# biochem_M.net
KiCad netlist of a schematic drawn in EAGLE
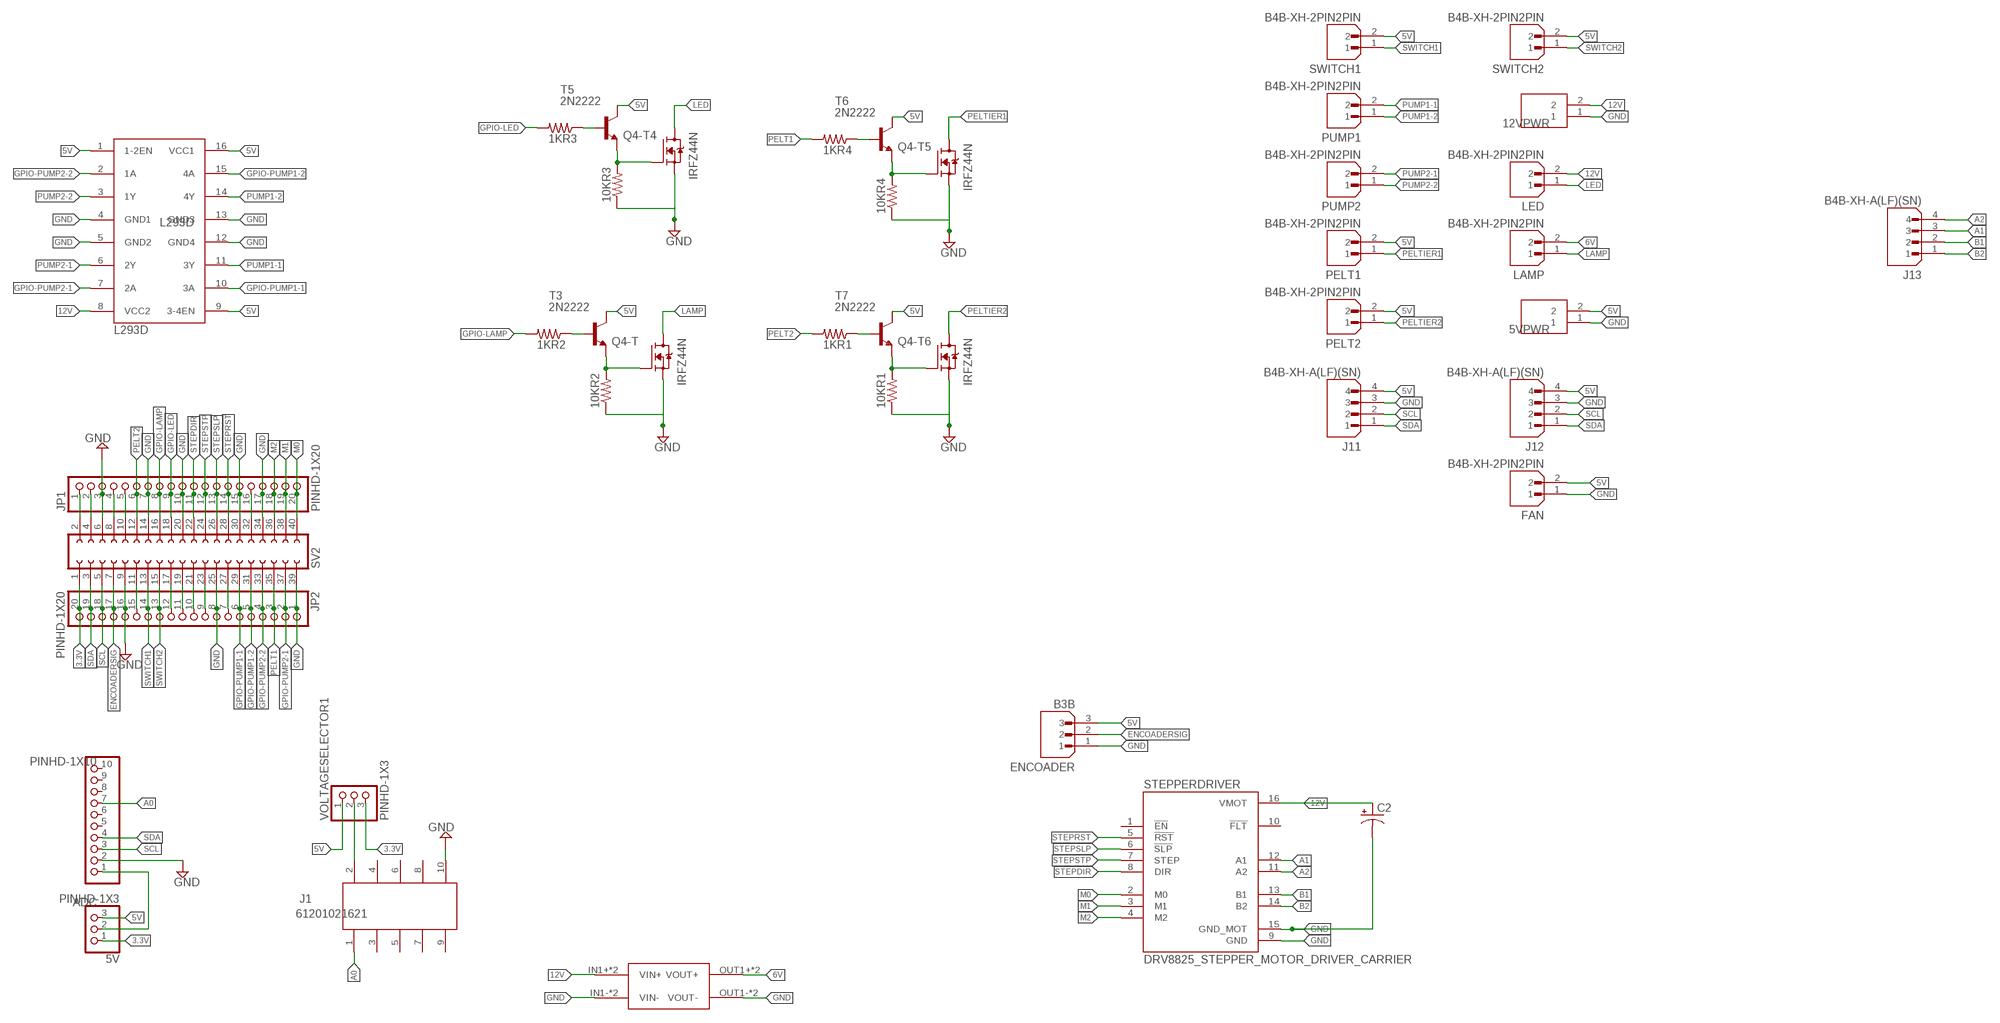
[diagram p0: schematic, sheet 1]

(export (version "E")
  (design (tool "Eeschema 10.0.6"))
  (components
    (comp (ref "1KR1")
      (value "R-US_0204/7")
      (footprint "eagle-import:0204_7")
      (libsource (lib "eagle-import") (part "R-US_0204/7"))
    )
    (comp (ref "1KR2")
      (value "R-US_0204/7")
      (footprint "eagle-import:0204_7")
      (libsource (lib "eagle-import") (part "R-US_0204/7"))
    )
    (comp (ref "1KR3")
      (value "R-US_0204/7")
      (footprint "eagle-import:0204_7")
      (libsource (lib "eagle-import") (part "R-US_0204/7"))
    )
    (comp (ref "1KR4")
      (value "R-US_0204/7")
      (footprint "eagle-import:0204_7")
      (libsource (lib "eagle-import") (part "R-US_0204/7"))
    )
    (comp (ref "5V")
      (value "PINHD-1X3")
      (footprint "eagle-import:1X03")
      (libsource (lib "eagle-import") (part "PINHD-1X3"))
    )
    (comp (ref "5VPWR")
      (value "TB010-508-02BE")
      (footprint "eagle-import:CUI_TB010-508-02BE")
      (fields (field (name "MF") "CUI Devices"))
      (libsource (lib "eagle-import") (part "TB010-508-02BE"))
    )
    (comp (ref "10KR1")
      (value "R-US_0204/7")
      (footprint "eagle-import:0204_7")
      (libsource (lib "eagle-import") (part "R-US_0204/7"))
    )
    (comp (ref "10KR2")
      (value "R-US_0204/7")
      (footprint "eagle-import:0204_7")
      (libsource (lib "eagle-import") (part "R-US_0204/7"))
    )
    (comp (ref "10KR3")
      (value "R-US_0204/7")
      (footprint "eagle-import:0204_7")
      (libsource (lib "eagle-import") (part "R-US_0204/7"))
    )
    (comp (ref "10KR4")
      (value "R-US_0204/7")
      (footprint "eagle-import:0204_7")
      (libsource (lib "eagle-import") (part "R-US_0204/7"))
    )
    (comp (ref "12VPWR")
      (value "TB010-508-02BE")
      (footprint "eagle-import:CUI_TB010-508-02BE")
      (fields (field (name "MF") "CUI Devices"))
      (libsource (lib "eagle-import") (part "TB010-508-02BE"))
    )
    (comp (ref "ADC")
      (value "PINHD-1X10")
      (footprint "eagle-import:1X10")
      (libsource (lib "eagle-import") (part "PINHD-1X10"))
    )
    (comp (ref "C2")
      (value "CPOL-USB45181A")
      (footprint "eagle-import:B45181A")
      (libsource (lib "eagle-import") (part "CPOL-USB45181A"))
    )
    (comp (ref "ENCOADER")
      (value "B3B")
      (footprint "eagle-import:B3B")
      (libsource (lib "eagle-import") (part "B3B"))
    )
    (comp (ref "FAN")
      (value "B4B-XH-2PIN2PIN")
      (footprint "eagle-import:B4BXH2")
      (libsource (lib "eagle-import") (part "B4B-XH-2PIN2PIN"))
    )
    (comp (ref "J1")
      (value "61201021621")
      (footprint "eagle-import:61201021621")
      (fields (field (name "MF") "Wurth Elektronik"))
      (libsource (lib "eagle-import") (part "61201021621"))
    )
    (comp (ref "J11")
      (value "B4B-XH-A(LF)(SN)")
      (footprint "eagle-import:JST_B4B-XH-A(LF)(SN)")
      (fields (field (name "MF") "JST") (field (name "MP") "B4B-XH-A  (LF)(SN)"))
      (libsource (lib "eagle-import") (part "B4B-XH-A(LF)(SN)"))
    )
    (comp (ref "J12")
      (value "B4B-XH-A(LF)(SN)")
      (footprint "eagle-import:JST_B4B-XH-A(LF)(SN)")
      (fields (field (name "MF") "JST") (field (name "MP") "B4B-XH-A  (LF)(SN)"))
      (libsource (lib "eagle-import") (part "B4B-XH-A(LF)(SN)"))
    )
    (comp (ref "J13")
      (value "B4B-XH-A(LF)(SN)")
      (footprint "eagle-import:JST_B4B-XH-A(LF)(SN)")
      (fields (field (name "MF") "JST") (field (name "MP") "B4B-XH-A  (LF)(SN)"))
      (libsource (lib "eagle-import") (part "B4B-XH-A(LF)(SN)"))
    )
    (comp (ref "JP1")
      (value "PINHD-1X20")
      (footprint "eagle-import:1X20")
      (libsource (lib "eagle-import") (part "PINHD-1X20"))
    )
    (comp (ref "JP2")
      (value "PINHD-1X20")
      (footprint "eagle-import:1X20")
      (libsource (lib "eagle-import") (part "PINHD-1X20"))
    )
    (comp (ref "L293D")
      (value "L293D")
      (footprint "eagle-import:DIL16")
      (libsource (lib "eagle-import") (part "L293D"))
    )
    (comp (ref "LAMP")
      (value "B4B-XH-2PIN2PIN")
      (footprint "eagle-import:B4BXH2")
      (libsource (lib "eagle-import") (part "B4B-XH-2PIN2PIN"))
    )
    (comp (ref "LED")
      (value "B4B-XH-2PIN2PIN")
      (footprint "eagle-import:B4BXH2")
      (libsource (lib "eagle-import") (part "B4B-XH-2PIN2PIN"))
    )
    (comp (ref "PELT1")
      (value "B4B-XH-2PIN2PIN")
      (footprint "eagle-import:B4BXH2")
      (libsource (lib "eagle-import") (part "B4B-XH-2PIN2PIN"))
    )
    (comp (ref "PELT2")
      (value "B4B-XH-2PIN2PIN")
      (footprint "eagle-import:B4BXH2")
      (libsource (lib "eagle-import") (part "B4B-XH-2PIN2PIN"))
    )
    (comp (ref "PUMP1")
      (value "B4B-XH-2PIN2PIN")
      (footprint "eagle-import:B4BXH2")
      (libsource (lib "eagle-import") (part "B4B-XH-2PIN2PIN"))
    )
    (comp (ref "PUMP2")
      (value "B4B-XH-2PIN2PIN")
      (footprint "eagle-import:B4BXH2")
      (libsource (lib "eagle-import") (part "B4B-XH-2PIN2PIN"))
    )
    (comp (ref "Q4-T")
      (value "IRFZ44N")
      (footprint "eagle-import:TO254P1016X419X2286-3")
      (fields (field (name "MF") "Infineon Technologies"))
      (libsource (lib "eagle-import") (part "IRFZ44N"))
    )
    (comp (ref "Q4-T4")
      (value "IRFZ44N")
      (footprint "eagle-import:TO254P1016X419X2286-3")
      (fields (field (name "MF") "Infineon Technologies"))
      (libsource (lib "eagle-import") (part "IRFZ44N"))
    )
    (comp (ref "Q4-T5")
      (value "IRFZ44N")
      (footprint "eagle-import:TO254P1016X419X2286-3")
      (fields (field (name "MF") "Infineon Technologies"))
      (libsource (lib "eagle-import") (part "IRFZ44N"))
    )
    (comp (ref "Q4-T6")
      (value "IRFZ44N")
      (footprint "eagle-import:TO254P1016X419X2286-3")
      (fields (field (name "MF") "Infineon Technologies"))
      (libsource (lib "eagle-import") (part "IRFZ44N"))
    )
    (comp (ref "STEPPERDRIVER")
      (value "DRV8825_STEPPER_MOTOR_DRIVER_CARRIER")
      (footprint "eagle-import:IC_DRV8825_STEPPER_MOTOR_DRIVER_CARRIER")
      (fields (field (name "MF") "Pololu") (field (name "MP") "DRV8825 STEPPER MOTOR DRIVER CARRIER"))
      (libsource (lib "eagle-import") (part "DRV8825_STEPPER_MOTOR_DRIVER_CARRIER"))
    )
    (comp (ref "SV2")
      (value "FE20-2")
      (footprint "eagle-import:FE20-2")
      (libsource (lib "eagle-import") (part "FE20-2"))
    )
    (comp (ref "SWITCH1")
      (value "B4B-XH-2PIN2PIN")
      (footprint "eagle-import:B4BXH2")
      (libsource (lib "eagle-import") (part "B4B-XH-2PIN2PIN"))
    )
    (comp (ref "SWITCH2")
      (value "B4B-XH-2PIN2PIN")
      (footprint "eagle-import:B4BXH2")
      (libsource (lib "eagle-import") (part "B4B-XH-2PIN2PIN"))
    )
    (comp (ref "T3")
      (value "2N2222")
      (footprint "eagle-import:TO92-EBC-OVAL")
      (libsource (lib "eagle-import") (part "2N2222"))
    )
    (comp (ref "T5")
      (value "2N2222")
      (footprint "eagle-import:TO92-EBC-OVAL")
      (libsource (lib "eagle-import") (part "2N2222"))
    )
    (comp (ref "T6")
      (value "2N2222")
      (footprint "eagle-import:TO92-EBC-OVAL")
      (libsource (lib "eagle-import") (part "2N2222"))
    )
    (comp (ref "T7")
      (value "2N2222")
      (footprint "eagle-import:TO92-EBC-OVAL")
      (libsource (lib "eagle-import") (part "2N2222"))
    )
    (comp (ref "U$1")
      (value "MP1584")
      (footprint "eagle-import:DC-BRICK")
      (libsource (lib "eagle-import") (part "MP1584"))
    )
    (comp (ref "VOLTAGESELECTOR1")
      (value "PINHD-1X3")
      (footprint "eagle-import:1X03")
      (libsource (lib "eagle-import") (part "PINHD-1X3"))
    )
  )
  (nets
    (net (code "1") (name "3.3V") (class "Default")
      (node (ref "5V") (pin "1") (pinfunction "1_1") (pintype "passive"))
      (node (ref "JP2") (pin "20") (pinfunction "20_20") (pintype "passive"))
      (node (ref "SV2") (pin "1") (pinfunction "1_1") (pintype "passive"))
      (node (ref "VOLTAGESELECTOR1") (pin "3") (pinfunction "3_3") (pintype "passive"))
    )
    (net (code "2") (name "5V") (class "Default")
      (node (ref "5V") (pin "3") (pinfunction "3_3") (pintype "passive"))
      (node (ref "5VPWR") (pin "2") (pinfunction "2_2") (pintype "passive"))
      (node (ref "ENCOADER") (pin "3") (pinfunction "3_3") (pintype "passive"))
      (node (ref "FAN") (pin "2") (pinfunction "2_2") (pintype "passive"))
      (node (ref "J11") (pin "4") (pinfunction "4_4") (pintype "passive"))
      (node (ref "J12") (pin "4") (pinfunction "4_4") (pintype "passive"))
      (node (ref "L293D") (pin "1") (pinfunction "1-2EN_1") (pintype "input"))
      (node (ref "L293D") (pin "16") (pinfunction "VCC1_16") (pintype "power_in"))
      (node (ref "L293D") (pin "9") (pinfunction "3-4EN_9") (pintype "input"))
      (node (ref "PELT1") (pin "2") (pinfunction "2_2") (pintype "passive"))
      (node (ref "PELT2") (pin "2") (pinfunction "2_2") (pintype "passive"))
      (node (ref "SWITCH1") (pin "2") (pinfunction "2_2") (pintype "passive"))
      (node (ref "SWITCH2") (pin "2") (pinfunction "2_2") (pintype "passive"))
      (node (ref "T3") (pin "C") (pinfunction "C_C") (pintype "passive"))
      (node (ref "T5") (pin "C") (pinfunction "C_C") (pintype "passive"))
      (node (ref "T6") (pin "C") (pinfunction "C_C") (pintype "passive"))
      (node (ref "T7") (pin "C") (pinfunction "C_C") (pintype "passive"))
      (node (ref "VOLTAGESELECTOR1") (pin "1") (pinfunction "1_1") (pintype "passive"))
    )
    (net (code "3") (name "6V") (class "Default")
      (node (ref "LAMP") (pin "2") (pinfunction "2_2") (pintype "passive"))
      (node (ref "U$1") (pin "OUT1+") (pinfunction "VOUT+_OUT1+") (pintype "output"))
      (node (ref "U$1") (pin "OUT2+") (pinfunction "VOUT+_OUT2+") (pintype "output"))
    )
    (net (code "4") (name "12V") (class "Default")
      (node (ref "12VPWR") (pin "2") (pinfunction "2_2") (pintype "passive"))
      (node (ref "C2") (pin "+") (pinfunction "+_+") (pintype "passive"))
      (node (ref "L293D") (pin "8") (pinfunction "VCC2_8") (pintype "power_in"))
      (node (ref "LED") (pin "2") (pinfunction "2_2") (pintype "passive"))
      (node (ref "STEPPERDRIVER") (pin "16") (pinfunction "VMOT_16") (pintype "power_in"))
      (node (ref "U$1") (pin "IN1+") (pinfunction "VIN+_IN1+") (pintype "input"))
      (node (ref "U$1") (pin "IN2+") (pinfunction "VIN+_IN2+") (pintype "input"))
    )
    (net (code "5") (name "A0") (class "Default")
      (node (ref "ADC") (pin "7") (pinfunction "7_7") (pintype "passive"))
      (node (ref "J1") (pin "1") (pinfunction "1_1") (pintype "passive"))
    )
    (net (code "6") (name "A1") (class "Default")
      (node (ref "J13") (pin "3") (pinfunction "3_3") (pintype "passive"))
      (node (ref "STEPPERDRIVER") (pin "12") (pinfunction "A1_12") (pintype "output"))
    )
    (net (code "7") (name "A2") (class "Default")
      (node (ref "J13") (pin "4") (pinfunction "4_4") (pintype "passive"))
      (node (ref "STEPPERDRIVER") (pin "11") (pinfunction "A2_11") (pintype "output"))
    )
    (net (code "8") (name "B1") (class "Default")
      (node (ref "J13") (pin "2") (pinfunction "2_2") (pintype "passive"))
      (node (ref "STEPPERDRIVER") (pin "13") (pinfunction "B1_13") (pintype "output"))
    )
    (net (code "9") (name "B2") (class "Default")
      (node (ref "J13") (pin "1") (pinfunction "1_1") (pintype "passive"))
      (node (ref "STEPPERDRIVER") (pin "14") (pinfunction "B2_14") (pintype "output"))
    )
    (net (code "10") (name "ENCOADERSIG") (class "Default")
      (node (ref "ENCOADER") (pin "2") (pinfunction "2_2") (pintype "passive"))
      (node (ref "JP2") (pin "17") (pinfunction "17_17") (pintype "passive"))
      (node (ref "SV2") (pin "7") (pinfunction "7_7") (pintype "passive"))
    )
    (net (code "11") (name "GND") (class "Default")
      (node (ref "10KR1") (pin "1") (pinfunction "1_1") (pintype "passive"))
      (node (ref "10KR2") (pin "1") (pinfunction "1_1") (pintype "passive"))
      (node (ref "10KR3") (pin "1") (pinfunction "1_1") (pintype "passive"))
      (node (ref "10KR4") (pin "1") (pinfunction "1_1") (pintype "passive"))
      (node (ref "12VPWR") (pin "1") (pinfunction "1_1") (pintype "passive"))
      (node (ref "5VPWR") (pin "1") (pinfunction "1_1") (pintype "passive"))
      (node (ref "ADC") (pin "2") (pinfunction "2_2") (pintype "passive"))
      (node (ref "C2") (pin "-") (pinfunction "-_-") (pintype "passive"))
      (node (ref "ENCOADER") (pin "1") (pinfunction "1_1") (pintype "passive"))
      (node (ref "FAN") (pin "1") (pinfunction "1_1") (pintype "passive"))
      (node (ref "J1") (pin "10") (pinfunction "10_10") (pintype "passive"))
      (node (ref "J11") (pin "3") (pinfunction "3_3") (pintype "passive"))
      (node (ref "J12") (pin "3") (pinfunction "3_3") (pintype "passive"))
      (node (ref "JP1") (pin "10") (pinfunction "10_10") (pintype "passive"))
      (node (ref "JP1") (pin "15") (pinfunction "15_15") (pintype "passive"))
      (node (ref "JP1") (pin "17") (pinfunction "17_17") (pintype "passive"))
      (node (ref "JP1") (pin "3") (pinfunction "3_3") (pintype "passive"))
      (node (ref "JP1") (pin "7") (pinfunction "7_7") (pintype "passive"))
      (node (ref "JP2") (pin "1") (pinfunction "1_1") (pintype "passive"))
      (node (ref "JP2") (pin "16") (pinfunction "16_16") (pintype "passive"))
      (node (ref "JP2") (pin "8") (pinfunction "8_8") (pintype "passive"))
      (node (ref "L293D") (pin "12") (pinfunction "GND4_12") (pintype "power_in"))
      (node (ref "L293D") (pin "13") (pinfunction "GND3_13") (pintype "power_in"))
      (node (ref "L293D") (pin "4") (pinfunction "GND1_4") (pintype "power_in"))
      (node (ref "L293D") (pin "5") (pinfunction "GND2_5") (pintype "power_in"))
      (node (ref "Q4-T") (pin "3") (pinfunction "S_3") (pintype "passive"))
      (node (ref "Q4-T4") (pin "3") (pinfunction "S_3") (pintype "passive"))
      (node (ref "Q4-T5") (pin "3") (pinfunction "S_3") (pintype "passive"))
      (node (ref "Q4-T6") (pin "3") (pinfunction "S_3") (pintype "passive"))
      (node (ref "STEPPERDRIVER") (pin "15") (pinfunction "GND_MOT_15") (pintype "power_in"))
      (node (ref "STEPPERDRIVER") (pin "9") (pinfunction "GND_9") (pintype "power_in"))
      (node (ref "SV2") (pin "14") (pinfunction "14_14") (pintype "passive"))
      (node (ref "SV2") (pin "20") (pinfunction "20_20") (pintype "passive"))
      (node (ref "SV2") (pin "25") (pinfunction "25_25") (pintype "passive"))
      (node (ref "SV2") (pin "30") (pinfunction "30_30") (pintype "passive"))
      (node (ref "SV2") (pin "34") (pinfunction "34_34") (pintype "passive"))
      (node (ref "SV2") (pin "39") (pinfunction "39_39") (pintype "passive"))
      (node (ref "SV2") (pin "6") (pinfunction "6_6") (pintype "passive"))
      (node (ref "SV2") (pin "9") (pinfunction "9_9") (pintype "passive"))
      (node (ref "U$1") (pin "IN1-") (pinfunction "VIN-_IN1-") (pintype "input"))
      (node (ref "U$1") (pin "IN2-") (pinfunction "VIN-_IN2-") (pintype "input"))
      (node (ref "U$1") (pin "OUT1-") (pinfunction "VOUT-_OUT1-") (pintype "output"))
      (node (ref "U$1") (pin "OUT2-") (pinfunction "VOUT-_OUT2-") (pintype "output"))
    )
    (net (code "12") (name "GPIO-LAMP") (class "Default")
      (node (ref "1KR2") (pin "2") (pinfunction "2_2") (pintype "passive"))
      (node (ref "JP1") (pin "8") (pinfunction "8_8") (pintype "passive"))
      (node (ref "SV2") (pin "16") (pinfunction "16_16") (pintype "passive"))
    )
    (net (code "13") (name "GPIO-LED") (class "Default")
      (node (ref "1KR3") (pin "2") (pinfunction "2_2") (pintype "passive"))
      (node (ref "JP1") (pin "9") (pinfunction "9_9") (pintype "passive"))
      (node (ref "SV2") (pin "18") (pinfunction "18_18") (pintype "passive"))
    )
    (net (code "14") (name "GPIO-PUMP1-1") (class "Default")
      (node (ref "JP2") (pin "6") (pinfunction "6_6") (pintype "passive"))
      (node (ref "L293D") (pin "10") (pinfunction "3A_10") (pintype "input"))
      (node (ref "SV2") (pin "29") (pinfunction "29_29") (pintype "passive"))
    )
    (net (code "15") (name "GPIO-PUMP1-2") (class "Default")
      (node (ref "JP2") (pin "5") (pinfunction "5_5") (pintype "passive"))
      (node (ref "L293D") (pin "15") (pinfunction "4A_15") (pintype "input"))
      (node (ref "SV2") (pin "31") (pinfunction "31_31") (pintype "passive"))
    )
    (net (code "16") (name "GPIO-PUMP2-1") (class "Default")
      (node (ref "JP2") (pin "2") (pinfunction "2_2") (pintype "passive"))
      (node (ref "L293D") (pin "7") (pinfunction "2A_7") (pintype "input"))
      (node (ref "SV2") (pin "37") (pinfunction "37_37") (pintype "passive"))
    )
    (net (code "17") (name "GPIO-PUMP2-2") (class "Default")
      (node (ref "JP2") (pin "4") (pinfunction "4_4") (pintype "passive"))
      (node (ref "L293D") (pin "2") (pinfunction "1A_2") (pintype "input"))
      (node (ref "SV2") (pin "33") (pinfunction "33_33") (pintype "passive"))
    )
    (net (code "18") (name "LAMP") (class "Default")
      (node (ref "LAMP") (pin "1") (pinfunction "1_1") (pintype "passive"))
      (node (ref "Q4-T") (pin "2") (pinfunction "D_2") (pintype "passive"))
    )
    (net (code "19") (name "LED") (class "Default")
      (node (ref "LED") (pin "1") (pinfunction "1_1") (pintype "passive"))
      (node (ref "Q4-T4") (pin "2") (pinfunction "D_2") (pintype "passive"))
    )
    (net (code "20") (name "M0") (class "Default")
      (node (ref "JP1") (pin "20") (pinfunction "20_20") (pintype "passive"))
      (node (ref "STEPPERDRIVER") (pin "2") (pinfunction "M0_2") (pintype "input"))
      (node (ref "SV2") (pin "40") (pinfunction "40_40") (pintype "passive"))
    )
    (net (code "21") (name "M1") (class "Default")
      (node (ref "JP1") (pin "19") (pinfunction "19_19") (pintype "passive"))
      (node (ref "STEPPERDRIVER") (pin "3") (pinfunction "M1_3") (pintype "input"))
      (node (ref "SV2") (pin "38") (pinfunction "38_38") (pintype "passive"))
    )
    (net (code "22") (name "M2") (class "Default")
      (node (ref "JP1") (pin "18") (pinfunction "18_18") (pintype "passive"))
      (node (ref "STEPPERDRIVER") (pin "4") (pinfunction "M2_4") (pintype "input"))
      (node (ref "SV2") (pin "36") (pinfunction "36_36") (pintype "passive"))
    )
    (net (code "23") (name "Net-(1KR1-Pad1)") (class "Default")
      (node (ref "1KR1") (pin "1") (pinfunction "1_1") (pintype "passive"))
      (node (ref "T7") (pin "B") (pinfunction "B_B") (pintype "passive"))
    )
    (net (code "24") (name "Net-(1KR2-Pad1)") (class "Default")
      (node (ref "1KR2") (pin "1") (pinfunction "1_1") (pintype "passive"))
      (node (ref "T3") (pin "B") (pinfunction "B_B") (pintype "passive"))
    )
    (net (code "25") (name "Net-(1KR3-Pad1)") (class "Default")
      (node (ref "1KR3") (pin "1") (pinfunction "1_1") (pintype "passive"))
      (node (ref "T5") (pin "B") (pinfunction "B_B") (pintype "passive"))
    )
    (net (code "26") (name "Net-(1KR4-Pad1)") (class "Default")
      (node (ref "1KR4") (pin "1") (pinfunction "1_1") (pintype "passive"))
      (node (ref "T6") (pin "B") (pinfunction "B_B") (pintype "passive"))
    )
    (net (code "27") (name "Net-(5V-Pad2)") (class "Default")
      (node (ref "5V") (pin "2") (pinfunction "2_2") (pintype "passive"))
      (node (ref "ADC") (pin "1") (pinfunction "1_1") (pintype "passive"))
    )
    (net (code "28") (name "Net-(J1-Pad2)") (class "Default")
      (node (ref "J1") (pin "2") (pinfunction "2_2") (pintype "passive"))
      (node (ref "VOLTAGESELECTOR1") (pin "2") (pinfunction "2_2") (pintype "passive"))
    )
    (net (code "29") (name "Net-(JP1-Pad1)") (class "Default")
      (node (ref "JP1") (pin "1") (pinfunction "1_1") (pintype "passive"))
      (node (ref "SV2") (pin "2") (pinfunction "2_2") (pintype "passive"))
    )
    (net (code "30") (name "Net-(JP1-Pad2)") (class "Default")
      (node (ref "JP1") (pin "2") (pinfunction "2_2") (pintype "passive"))
      (node (ref "SV2") (pin "4") (pinfunction "4_4") (pintype "passive"))
    )
    (net (code "31") (name "Net-(JP1-Pad4)") (class "Default")
      (node (ref "JP1") (pin "4") (pinfunction "4_4") (pintype "passive"))
      (node (ref "SV2") (pin "8") (pinfunction "8_8") (pintype "passive"))
    )
    (net (code "32") (name "Net-(JP1-Pad5)") (class "Default")
      (node (ref "JP1") (pin "5") (pinfunction "5_5") (pintype "passive"))
      (node (ref "SV2") (pin "10") (pinfunction "10_10") (pintype "passive"))
    )
    (net (code "33") (name "Net-(JP1-Pad16)") (class "Default")
      (node (ref "JP1") (pin "16") (pinfunction "16_16") (pintype "passive"))
      (node (ref "SV2") (pin "32") (pinfunction "32_32") (pintype "passive"))
    )
    (net (code "34") (name "Net-(JP2-Pad7)") (class "Default")
      (node (ref "JP2") (pin "7") (pinfunction "7_7") (pintype "passive"))
      (node (ref "SV2") (pin "27") (pinfunction "27_27") (pintype "passive"))
    )
    (net (code "35") (name "Net-(JP2-Pad9)") (class "Default")
      (node (ref "JP2") (pin "9") (pinfunction "9_9") (pintype "passive"))
      (node (ref "SV2") (pin "23") (pinfunction "23_23") (pintype "passive"))
    )
    (net (code "36") (name "Net-(JP2-Pad10)") (class "Default")
      (node (ref "JP2") (pin "10") (pinfunction "10_10") (pintype "passive"))
      (node (ref "SV2") (pin "21") (pinfunction "21_21") (pintype "passive"))
    )
    (net (code "37") (name "Net-(JP2-Pad11)") (class "Default")
      (node (ref "JP2") (pin "11") (pinfunction "11_11") (pintype "passive"))
      (node (ref "SV2") (pin "19") (pinfunction "19_19") (pintype "passive"))
    )
    (net (code "38") (name "Net-(JP2-Pad12)") (class "Default")
      (node (ref "JP2") (pin "12") (pinfunction "12_12") (pintype "passive"))
      (node (ref "SV2") (pin "17") (pinfunction "17_17") (pintype "passive"))
    )
    (net (code "39") (name "Net-(JP2-Pad15)") (class "Default")
      (node (ref "JP2") (pin "15") (pinfunction "15_15") (pintype "passive"))
      (node (ref "SV2") (pin "11") (pinfunction "11_11") (pintype "passive"))
    )
    (net (code "40") (name "Net-(Q4-T-G)") (class "Default")
      (node (ref "10KR2") (pin "2") (pinfunction "2_2") (pintype "passive"))
      (node (ref "Q4-T") (pin "1") (pinfunction "G_1") (pintype "passive"))
      (node (ref "T3") (pin "E") (pinfunction "E_E") (pintype "passive"))
    )
    (net (code "41") (name "Net-(Q4-T4-G)") (class "Default")
      (node (ref "10KR3") (pin "2") (pinfunction "2_2") (pintype "passive"))
      (node (ref "Q4-T4") (pin "1") (pinfunction "G_1") (pintype "passive"))
      (node (ref "T5") (pin "E") (pinfunction "E_E") (pintype "passive"))
    )
    (net (code "42") (name "Net-(Q4-T5-G)") (class "Default")
      (node (ref "10KR4") (pin "2") (pinfunction "2_2") (pintype "passive"))
      (node (ref "Q4-T5") (pin "1") (pinfunction "G_1") (pintype "passive"))
      (node (ref "T6") (pin "E") (pinfunction "E_E") (pintype "passive"))
    )
    (net (code "43") (name "Net-(Q4-T6-G)") (class "Default")
      (node (ref "10KR1") (pin "2") (pinfunction "2_2") (pintype "passive"))
      (node (ref "Q4-T6") (pin "1") (pinfunction "G_1") (pintype "passive"))
      (node (ref "T7") (pin "E") (pinfunction "E_E") (pintype "passive"))
    )
    (net (code "44") (name "PELT1") (class "Default")
      (node (ref "1KR4") (pin "2") (pinfunction "2_2") (pintype "passive"))
      (node (ref "JP2") (pin "3") (pinfunction "3_3") (pintype "passive"))
      (node (ref "SV2") (pin "35") (pinfunction "35_35") (pintype "passive"))
    )
    (net (code "45") (name "PELT2") (class "Default")
      (node (ref "1KR1") (pin "2") (pinfunction "2_2") (pintype "passive"))
      (node (ref "JP1") (pin "6") (pinfunction "6_6") (pintype "passive"))
      (node (ref "SV2") (pin "12") (pinfunction "12_12") (pintype "passive"))
    )
    (net (code "46") (name "PELTIER1") (class "Default")
      (node (ref "PELT1") (pin "1") (pinfunction "1_1") (pintype "passive"))
      (node (ref "Q4-T5") (pin "2") (pinfunction "D_2") (pintype "passive"))
    )
    (net (code "47") (name "PELTIER2") (class "Default")
      (node (ref "PELT2") (pin "1") (pinfunction "1_1") (pintype "passive"))
      (node (ref "Q4-T6") (pin "2") (pinfunction "D_2") (pintype "passive"))
    )
    (net (code "48") (name "PUMP1-1") (class "Default")
      (node (ref "L293D") (pin "11") (pinfunction "3Y_11") (pintype "output"))
      (node (ref "PUMP1") (pin "2") (pinfunction "2_2") (pintype "passive"))
    )
    (net (code "49") (name "PUMP1-2") (class "Default")
      (node (ref "L293D") (pin "14") (pinfunction "4Y_14") (pintype "output"))
      (node (ref "PUMP1") (pin "1") (pinfunction "1_1") (pintype "passive"))
    )
    (net (code "50") (name "PUMP2-1") (class "Default")
      (node (ref "L293D") (pin "6") (pinfunction "2Y_6") (pintype "output"))
      (node (ref "PUMP2") (pin "2") (pinfunction "2_2") (pintype "passive"))
    )
    (net (code "51") (name "PUMP2-2") (class "Default")
      (node (ref "L293D") (pin "3") (pinfunction "1Y_3") (pintype "output"))
      (node (ref "PUMP2") (pin "1") (pinfunction "1_1") (pintype "passive"))
    )
    (net (code "52") (name "SCL") (class "Default")
      (node (ref "ADC") (pin "3") (pinfunction "3_3") (pintype "passive"))
      (node (ref "J11") (pin "2") (pinfunction "2_2") (pintype "passive"))
      (node (ref "J12") (pin "2") (pinfunction "2_2") (pintype "passive"))
      (node (ref "JP2") (pin "18") (pinfunction "18_18") (pintype "passive"))
      (node (ref "SV2") (pin "5") (pinfunction "5_5") (pintype "passive"))
    )
    (net (code "53") (name "SDA") (class "Default")
      (node (ref "ADC") (pin "4") (pinfunction "4_4") (pintype "passive"))
      (node (ref "J11") (pin "1") (pinfunction "1_1") (pintype "passive"))
      (node (ref "J12") (pin "1") (pinfunction "1_1") (pintype "passive"))
      (node (ref "JP2") (pin "19") (pinfunction "19_19") (pintype "passive"))
      (node (ref "SV2") (pin "3") (pinfunction "3_3") (pintype "passive"))
    )
    (net (code "54") (name "STEPDIR") (class "Default")
      (node (ref "JP1") (pin "11") (pinfunction "11_11") (pintype "passive"))
      (node (ref "STEPPERDRIVER") (pin "8") (pinfunction "DIR_8") (pintype "input"))
      (node (ref "SV2") (pin "22") (pinfunction "22_22") (pintype "passive"))
    )
    (net (code "55") (name "STEPRST") (class "Default")
      (node (ref "JP1") (pin "14") (pinfunction "14_14") (pintype "passive"))
      (node (ref "STEPPERDRIVER") (pin "5") (pinfunction "~{RST}_5") (pintype "input"))
      (node (ref "SV2") (pin "28") (pinfunction "28_28") (pintype "passive"))
    )
    (net (code "56") (name "STEPSLP") (class "Default")
      (node (ref "JP1") (pin "13") (pinfunction "13_13") (pintype "passive"))
      (node (ref "STEPPERDRIVER") (pin "6") (pinfunction "~{SLP}_6") (pintype "input"))
      (node (ref "SV2") (pin "26") (pinfunction "26_26") (pintype "passive"))
    )
    (net (code "57") (name "STEPSTP") (class "Default")
      (node (ref "JP1") (pin "12") (pinfunction "12_12") (pintype "passive"))
      (node (ref "STEPPERDRIVER") (pin "7") (pinfunction "STEP_7") (pintype "input"))
      (node (ref "SV2") (pin "24") (pinfunction "24_24") (pintype "passive"))
    )
    (net (code "58") (name "SWITCH1") (class "Default")
      (node (ref "JP2") (pin "14") (pinfunction "14_14") (pintype "passive"))
      (node (ref "SV2") (pin "13") (pinfunction "13_13") (pintype "passive"))
      (node (ref "SWITCH1") (pin "1") (pinfunction "1_1") (pintype "passive"))
    )
    (net (code "59") (name "SWITCH2") (class "Default")
      (node (ref "JP2") (pin "13") (pinfunction "13_13") (pintype "passive"))
      (node (ref "SV2") (pin "15") (pinfunction "15_15") (pintype "passive"))
      (node (ref "SWITCH2") (pin "1") (pinfunction "1_1") (pintype "passive"))
    )
    (net (code "60") (name "unconnected-(ADC-Pad5)") (class "Default")
      (node (ref "ADC") (pin "5") (pinfunction "5_5") (pintype "passive"))
    )
    (net (code "61") (name "unconnected-(ADC-Pad6)") (class "Default")
      (node (ref "ADC") (pin "6") (pinfunction "6_6") (pintype "passive"))
    )
    (net (code "62") (name "unconnected-(ADC-Pad8)") (class "Default")
      (node (ref "ADC") (pin "8") (pinfunction "8_8") (pintype "passive"))
    )
    (net (code "63") (name "unconnected-(ADC-Pad9)") (class "Default")
      (node (ref "ADC") (pin "9") (pinfunction "9_9") (pintype "passive"))
    )
    (net (code "64") (name "unconnected-(ADC-Pad10)") (class "Default")
      (node (ref "ADC") (pin "10") (pinfunction "10_10") (pintype "passive"))
    )
    (net (code "65") (name "unconnected-(J1-Pad3)") (class "Default")
      (node (ref "J1") (pin "3") (pinfunction "3_3") (pintype "passive"))
    )
    (net (code "66") (name "unconnected-(J1-Pad4)") (class "Default")
      (node (ref "J1") (pin "4") (pinfunction "4_4") (pintype "passive"))
    )
    (net (code "67") (name "unconnected-(J1-Pad5)") (class "Default")
      (node (ref "J1") (pin "5") (pinfunction "5_5") (pintype "passive"))
    )
    (net (code "68") (name "unconnected-(J1-Pad6)") (class "Default")
      (node (ref "J1") (pin "6") (pinfunction "6_6") (pintype "passive"))
    )
    (net (code "69") (name "unconnected-(J1-Pad7)") (class "Default")
      (node (ref "J1") (pin "7") (pinfunction "7_7") (pintype "passive"))
    )
    (net (code "70") (name "unconnected-(J1-Pad8)") (class "Default")
      (node (ref "J1") (pin "8") (pinfunction "8_8") (pintype "passive"))
    )
    (net (code "71") (name "unconnected-(J1-Pad9)") (class "Default")
      (node (ref "J1") (pin "9") (pinfunction "9_9") (pintype "passive"))
    )
    (net (code "72") (name "unconnected-(STEPPERDRIVER-~{EN}-Pad1)") (class "Default")
      (node (ref "STEPPERDRIVER") (pin "1") (pinfunction "~{EN}_1") (pintype "input"))
    )
    (net (code "73") (name "unconnected-(STEPPERDRIVER-~{FLT}-Pad10)") (class "Default")
      (node (ref "STEPPERDRIVER") (pin "10") (pinfunction "~{FLT}_10") (pintype "output"))
    )
  )
)
